# ADC_REF_07.net
KiCad netlist of a schematic drawn in Altium Designer
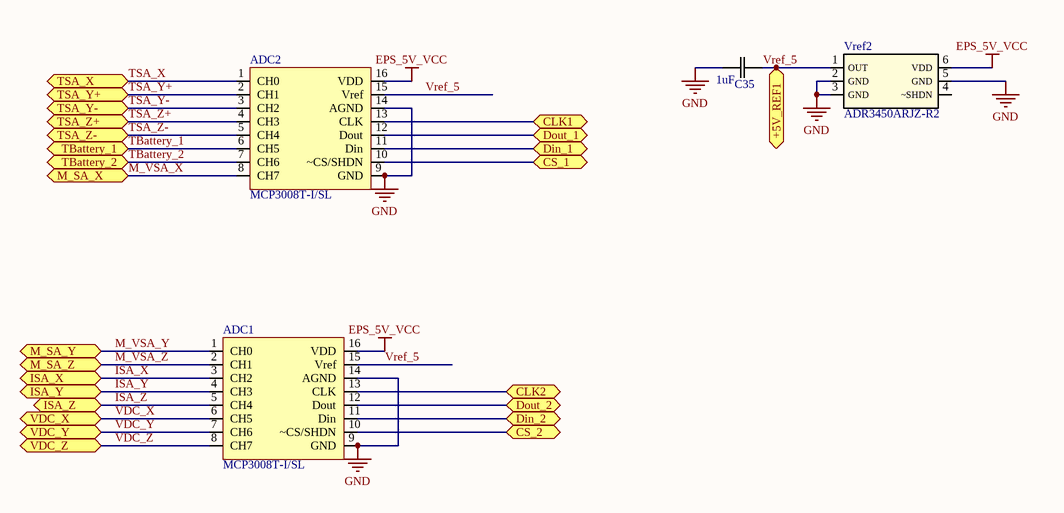
[diagram p0: ADC_REF_07.SchDoc]

(export (version "E")
  (design (tool "Eeschema 10.0.6"))
  (components
    (comp (ref "ADC1")
      (value "MCP3008T-I/SL")
      (footprint "SOIC16_L")
      (description "Analog  to Digital Converter, 10BIT 8 Channel")
      (fields (field (name "DIGI-KEY PART NUMBER") "MCP3008T-I/SLCT-ND"))
      (libsource (lib "PCDU_Library") (part "MCP3008T-I/SL"))
    )
    (comp (ref "ADC2")
      (value "MCP3008T-I/SL")
      (footprint "SOIC16_L")
      (description "Analog  to Digital Converter, 10BIT 8 Channel")
      (fields (field (name "DIGI-KEY PART NUMBER") "MCP3008T-I/SLCT-ND"))
      (libsource (lib "PCDU_Library") (part "MCP3008T-I/SL"))
    )
    (comp (ref "C35")
      (value "1uF")
      (footprint "0805")
      (description "Ceramic Capacitor 0402")
      (fields
        (field (name "MANUFACTURER_PART_NUMBER") "GRM155R71H103KA88D")
        (field (name "COPYRIGHT") "Copyright (C) 2015 Accelerated Designs. All rights reserved")
      )
      (libsource (lib "EPS_lib") (part "GRM155R71H103KA8"))
    )
    (comp (ref "Vref2")
      (value "ADR3450ARJZ-R2")
      (footprint "RJ_6-M")
      (description "Voltage Reference")
      (fields (field (name "MANUFACTURER_PART_NUMBER") "adr3412arjz-r2"))
      (libsource (lib "EPS_lib") (part "ADR3412ARJZ-R2"))
    )
  )
  (nets
    (net (code "1") (name "/CLK1") (class "Default")
      (node (ref "ADC2") (pin "13") (pinfunction "CLK_13") (pintype "passive"))
    )
    (net (code "2") (name "/CLK2") (class "Default")
      (node (ref "ADC1") (pin "13") (pinfunction "CLK_13") (pintype "passive"))
    )
    (net (code "3") (name "/CS_1") (class "Default")
      (node (ref "ADC2") (pin "10") (pinfunction "~CS/SHDN_10") (pintype "passive"))
    )
    (net (code "4") (name "/CS_2") (class "Default")
      (node (ref "ADC1") (pin "10") (pinfunction "~CS/SHDN_10") (pintype "passive"))
    )
    (net (code "5") (name "/Din_1") (class "Default")
      (node (ref "ADC2") (pin "11") (pinfunction "Din_11") (pintype "passive"))
    )
    (net (code "6") (name "/Din_2") (class "Default")
      (node (ref "ADC1") (pin "11") (pinfunction "Din_11") (pintype "passive"))
    )
    (net (code "7") (name "/Dout_1") (class "Default")
      (node (ref "ADC2") (pin "12") (pinfunction "Dout_12") (pintype "passive"))
    )
    (net (code "8") (name "/Dout_2") (class "Default")
      (node (ref "ADC1") (pin "12") (pinfunction "Dout_12") (pintype "passive"))
    )
    (net (code "9") (name "/ISA_X") (class "Default")
      (node (ref "ADC1") (pin "3") (pinfunction "CH2_3") (pintype "passive"))
    )
    (net (code "10") (name "/ISA_Y") (class "Default")
      (node (ref "ADC1") (pin "4") (pinfunction "CH3_4") (pintype "passive"))
    )
    (net (code "11") (name "/ISA_Z") (class "Default")
      (node (ref "ADC1") (pin "5") (pinfunction "CH4_5") (pintype "passive"))
    )
    (net (code "12") (name "/M_VSA_X") (class "Default")
      (node (ref "ADC2") (pin "8") (pinfunction "CH7_8") (pintype "passive"))
    )
    (net (code "13") (name "/M_VSA_Y") (class "Default")
      (node (ref "ADC1") (pin "1") (pinfunction "CH0_1") (pintype "passive"))
    )
    (net (code "14") (name "/M_VSA_Z") (class "Default")
      (node (ref "ADC1") (pin "2") (pinfunction "CH1_2") (pintype "passive"))
    )
    (net (code "15") (name "/TBattery_1") (class "Default")
      (node (ref "ADC2") (pin "6") (pinfunction "CH5_6") (pintype "passive"))
    )
    (net (code "16") (name "/TBattery_2") (class "Default")
      (node (ref "ADC2") (pin "7") (pinfunction "CH6_7") (pintype "passive"))
    )
    (net (code "17") (name "/TSA_X") (class "Default")
      (node (ref "ADC2") (pin "1") (pinfunction "CH0_1") (pintype "passive"))
    )
    (net (code "18") (name "/TSA_Y+") (class "Default")
      (node (ref "ADC2") (pin "2") (pinfunction "CH1_2") (pintype "passive"))
    )
    (net (code "19") (name "/TSA_Y-") (class "Default")
      (node (ref "ADC2") (pin "3") (pinfunction "CH2_3") (pintype "passive"))
    )
    (net (code "20") (name "/TSA_Z+") (class "Default")
      (node (ref "ADC2") (pin "4") (pinfunction "CH3_4") (pintype "passive"))
    )
    (net (code "21") (name "/TSA_Z-") (class "Default")
      (node (ref "ADC2") (pin "5") (pinfunction "CH4_5") (pintype "passive"))
    )
    (net (code "22") (name "/VDC_X") (class "Default")
      (node (ref "ADC1") (pin "6") (pinfunction "CH5_6") (pintype "passive"))
    )
    (net (code "23") (name "/VDC_Y") (class "Default")
      (node (ref "ADC1") (pin "7") (pinfunction "CH6_7") (pintype "passive"))
    )
    (net (code "24") (name "/VDC_Z") (class "Default")
      (node (ref "ADC1") (pin "8") (pinfunction "CH7_8") (pintype "passive"))
    )
    (net (code "25") (name "/Vref_5") (class "Default")
      (node (ref "ADC1") (pin "15") (pinfunction "Vref_15") (pintype "passive"))
      (node (ref "ADC2") (pin "15") (pinfunction "Vref_15") (pintype "passive"))
      (node (ref "C35") (pin "2") (pinfunction "2_2") (pintype "passive"))
      (node (ref "Vref2") (pin "1") (pinfunction "OUT_1") (pintype "passive"))
    )
    (net (code "26") (name "EPS_5V_VCC") (class "Default")
      (node (ref "ADC1") (pin "16") (pinfunction "VDD_16") (pintype "passive"))
      (node (ref "ADC2") (pin "16") (pinfunction "VDD_16") (pintype "passive"))
      (node (ref "Vref2") (pin "6") (pinfunction "VDD_6") (pintype "passive"))
    )
    (net (code "27") (name "GND") (class "Default")
      (node (ref "ADC1") (pin "14") (pinfunction "AGND_14") (pintype "passive"))
      (node (ref "ADC1") (pin "9") (pinfunction "GND_9") (pintype "passive"))
      (node (ref "ADC2") (pin "14") (pinfunction "AGND_14") (pintype "passive"))
      (node (ref "ADC2") (pin "9") (pinfunction "GND_9") (pintype "passive"))
      (node (ref "C35") (pin "1") (pinfunction "1_1") (pintype "passive"))
      (node (ref "Vref2") (pin "2") (pinfunction "GND_2") (pintype "passive"))
      (node (ref "Vref2") (pin "3") (pinfunction "GND_3") (pintype "passive"))
      (node (ref "Vref2") (pin "5") (pinfunction "GND_5") (pintype "passive"))
    )
    (net (code "28") (name "unconnected-(Vref2-~SHDN-Pad4)") (class "Default")
      (node (ref "Vref2") (pin "4") (pinfunction "~SHDN_4") (pintype "passive"))
    )
  )
)
